# LM2587.net
KiCad netlist of a schematic drawn in Altium Designer
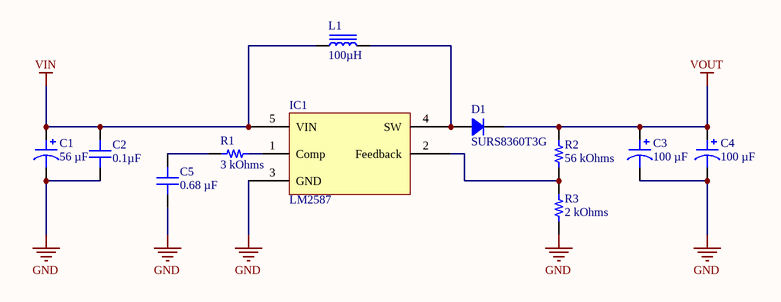
[diagram p0: LM2587.SchDoc]

(export (version "E")
  (design (tool "Eeschema 10.0.6"))
  (components
    (comp (ref "C1")
      (value "56 µF")
      (footprint "CAP ALSMD 6.6MM H7.7MM")
      (description "CAP ALUM 56UF 20% 35V SMD")
      (fields (field (name "PART NUMBER") "UWD1V560MCL1GS") (field (name "MANUFACTURER") "Nichicon"))
      (libsource (lib "Celestial Altium Library - altium_library") (part "Polarised Capacitor"))
    )
    (comp (ref "C2")
      (value "0.1µF")
      (footprint "CAP 0805_2012")
      (description "CAP CER 0.1UF 50V X7R 0805")
      (fields
        (field (name "PART NUMBER") "MM055C104KCZ2A")
        (field (name "CAPACITANCE") "0.1µF")
        (field (name "MANUFACTURER") "AVX Corporation")
      )
      (libsource (lib "Celestial Altium Library - altium_library") (part "Capacitor"))
    )
    (comp (ref "C3")
      (value "100 µF")
      (footprint "CAP ALSMD 8.3MM H10.5MM")
      (description "CAP ALUM 100UF 20% 50V SMD")
      (fields
        (field (name "PART NUMBER") "EEE-FK1H101P")
        (field (name "MANUFACTURER") "Panasonic Electronic Components")
      )
      (libsource (lib "Celestial Altium Library - altium_library") (part "Polarised Capacitor"))
    )
    (comp (ref "C4")
      (value "100 µF")
      (footprint "CAP ALSMD 8.3MM H10.5MM")
      (description "CAP ALUM 100UF 20% 50V SMD")
      (fields
        (field (name "PART NUMBER") "EEE-FK1H101P")
        (field (name "MANUFACTURER") "Panasonic Electronic Components")
      )
      (libsource (lib "Celestial Altium Library - altium_library") (part "Polarised Capacitor"))
    )
    (comp (ref "C5")
      (value "0.68 µF")
      (footprint "CAP 0805_2012")
      (description "CAP CER 0.68UF 50V X7R 0805")
      (fields
        (field (name "PART NUMBER") "C0805C684K5RACAUTO7210")
        (field (name "CAPACITANCE") "0.68 µF")
        (field (name "MANUFACTURER") "KEMET")
      )
      (libsource (lib "Celestial Altium Library - altium_library") (part "Capacitor"))
    )
    (comp (ref "D1")
      (value "SURS8360T3G")
      (footprint "DO214AB SMC")
      (description "DIODE GEN PURP 600V 3A SMC")
      (fields (field (name "MANUFACTURER") "ON Semiconductor"))
      (libsource (lib "Celestial Altium Library - altium_library") (part "Diode"))
    )
    (comp (ref "IC1")
      (value "LM2587")
      (footprint "D2PAK")
      (description "Boost")
      (libsource (lib "LM2587") (part "LM2587"))
    )
    (comp (ref "L1")
      (value "100µH")
      (footprint "7447070")
      (description "FIXED IND 100UH 450MA 540 MOHM")
      (fields
        (field (name "PART NUMBER") "SLF7032T-101MR45-2PF")
        (field (name "MANUFACTURER") "TDK Corporation")
      )
      (libsource (lib "Celestial Altium Library - altium_library") (part "Inductor"))
    )
    (comp (ref "R1")
      (value "3 kOhms")
      (footprint "RES 0805_2012")
      (description "RES 3K OHM 0.1% 1/8W 0805")
      (fields (field (name "PART NUMBER") "TNPW08053K00BYEN") (field (name "MANUFACTURER") "Vishay Dale"))
      (libsource (lib "Celestial Altium Library - altium_library") (part "Resistor"))
    )
    (comp (ref "R2")
      (value "56 kOhms")
      (footprint "RES 0805_2012")
      (description "RES 56K OHM 1% 1/8W 0805")
      (fields
        (field (name "PART NUMBER") "RMCF0805FT56K0")
        (field (name "MANUFACTURER") "Stackpole Electronics Inc")
      )
      (libsource (lib "Celestial Altium Library - altium_library") (part "Resistor"))
    )
    (comp (ref "R3")
      (value "2 kOhms")
      (footprint "RES 0805_2012")
      (description "RES 2K OHM 1% 1/8W 0805")
      (fields (field (name "PART NUMBER") "TNPW08052K00FEEA") (field (name "MANUFACTURER") "Vishay Dale"))
      (libsource (lib "Celestial Altium Library - altium_library") (part "Resistor"))
    )
  )
  (nets
    (net (code "1") (name "GND") (class "Default")
      (node (ref "C1") (pin "2") (pinfunction "2_2") (pintype "passive"))
      (node (ref "C2") (pin "1") (pinfunction "1_1") (pintype "passive"))
      (node (ref "C3") (pin "2") (pinfunction "2_2") (pintype "passive"))
      (node (ref "C4") (pin "2") (pinfunction "2_2") (pintype "passive"))
      (node (ref "C5") (pin "1") (pinfunction "1_1") (pintype "passive"))
      (node (ref "IC1") (pin "3") (pinfunction "GND_3") (pintype "passive"))
      (node (ref "R3") (pin "1") (pinfunction "1_1") (pintype "passive"))
    )
    (net (code "2") (name "Net-(C5-Pad2)") (class "Default")
      (node (ref "C5") (pin "2") (pinfunction "2_2") (pintype "passive"))
      (node (ref "R1") (pin "1") (pinfunction "1_1") (pintype "passive"))
    )
    (net (code "3") (name "Net-(IC1-Comp)") (class "Default")
      (node (ref "IC1") (pin "1") (pinfunction "Comp_1") (pintype "passive"))
      (node (ref "R1") (pin "2") (pinfunction "2_2") (pintype "passive"))
    )
    (net (code "4") (name "Net-(IC1-Feedback)") (class "Default")
      (node (ref "IC1") (pin "2") (pinfunction "Feedback_2") (pintype "passive"))
      (node (ref "R2") (pin "1") (pinfunction "1_1") (pintype "passive"))
      (node (ref "R3") (pin "2") (pinfunction "2_2") (pintype "passive"))
    )
    (net (code "5") (name "Net-(IC1-SW)") (class "Default")
      (node (ref "D1") (pin "1") (pinfunction "1_1") (pintype "passive"))
      (node (ref "IC1") (pin "4") (pinfunction "SW_4") (pintype "passive"))
      (node (ref "L1") (pin "2") (pinfunction "2_2") (pintype "passive"))
    )
    (net (code "6") (name "VIN") (class "Default")
      (node (ref "C1") (pin "1") (pinfunction "1_1") (pintype "passive"))
      (node (ref "C2") (pin "2") (pinfunction "2_2") (pintype "passive"))
      (node (ref "IC1") (pin "5") (pinfunction "VIN_5") (pintype "passive"))
      (node (ref "L1") (pin "1") (pinfunction "1_1") (pintype "passive"))
    )
    (net (code "7") (name "VOUT") (class "Default")
      (node (ref "C3") (pin "1") (pinfunction "1_1") (pintype "passive"))
      (node (ref "C4") (pin "1") (pinfunction "1_1") (pintype "passive"))
      (node (ref "D1") (pin "2") (pinfunction "2_2") (pintype "passive"))
      (node (ref "R2") (pin "2") (pinfunction "2_2") (pintype "passive"))
    )
  )
)
